# Rth.net
KiCad netlist of a schematic drawn in Altium Designer
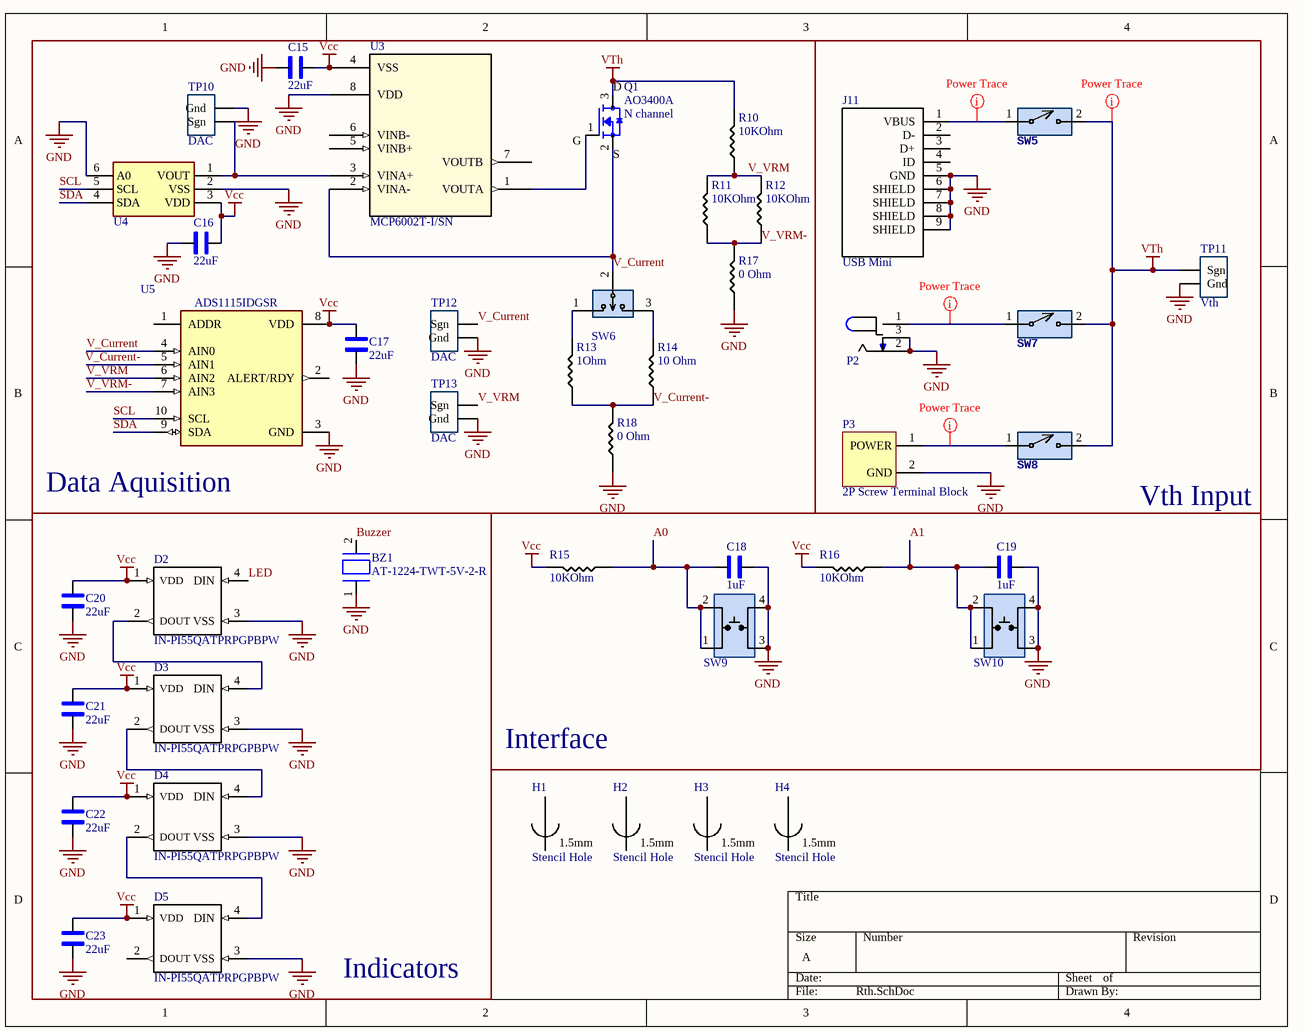
[diagram p0: Rth.SchDoc]

(export (version "E")
  (design (tool "Eeschema 10.0.6"))
  (components
    (comp (ref "BZ1")
      (value "AT-1224-TWT-5V-2-R")
      (footprint "BUZZER- TH")
      (fields (field (name "MFR PART #") "AT-1224-TWT-5V-2-R"))
      (libsource (lib "ECEN5730Lib_2023_01_DS") (part "BUZZER_1"))
    )
    (comp (ref "C15")
      (value "22uF")
      (footprint "1206_Passive_Capacitor")
      (description "22uF ±10% 25V X5R 1206 Multilayer Ceramic Capacitors MLCC - SMD/SMT RoHS")
      (fields (field (name "MFR PART #") "CL31A226KAHNNNE") (field (name "LCSC PART#") "C12891"))
      (libsource (lib "ECEN5730Lib_2023_01_DS") (part "C_22uF_1206"))
    )
    (comp (ref "C16")
      (value "22uF")
      (footprint "1206_Passive_Capacitor")
      (description "22uF ±10% 25V X5R 1206 Multilayer Ceramic Capacitors MLCC - SMD/SMT RoHS")
      (fields (field (name "MFR PART #") "CL31A226KAHNNNE") (field (name "LCSC PART#") "C12891"))
      (libsource (lib "ECEN5730Lib_2023_01_DS") (part "C_22uF_1206"))
    )
    (comp (ref "C17")
      (value "22uF")
      (footprint "1206_Passive_Capacitor")
      (description "22uF ±10% 25V X5R 1206 Multilayer Ceramic Capacitors MLCC - SMD/SMT RoHS")
      (fields (field (name "MFR PART #") "CL31A226KAHNNNE") (field (name "LCSC PART#") "C12891"))
      (libsource (lib "ECEN5730Lib_2023_01_DS") (part "C_22uF_1206"))
    )
    (comp (ref "C18")
      (value "1uF")
      (footprint "1206_Passive_Capacitor")
      (description "MULTILAYER CERAMIC CAPACITORS MLCC - SMD/SMT 1UF 50V 1206 ROHS")
      (fields (field (name "MFR PART #") "CL31B105KBHNNNE") (field (name "LCSC PART#") "C1848"))
      (libsource (lib "ECEN5730Lib_2023_01_DS") (part "C_1uF_1206"))
    )
    (comp (ref "C19")
      (value "1uF")
      (footprint "1206_Passive_Capacitor")
      (description "MULTILAYER CERAMIC CAPACITORS MLCC - SMD/SMT 1UF 50V 1206 ROHS")
      (fields (field (name "MFR PART #") "CL31B105KBHNNNE") (field (name "LCSC PART#") "C1848"))
      (libsource (lib "ECEN5730Lib_2023_01_DS") (part "C_1uF_1206"))
    )
    (comp (ref "C20")
      (value "22uF")
      (footprint "1206_Passive_Capacitor")
      (description "22uF ±10% 25V X5R 1206 Multilayer Ceramic Capacitors MLCC - SMD/SMT RoHS")
      (fields (field (name "MFR PART #") "CL31A226KAHNNNE") (field (name "LCSC PART#") "C12891"))
      (libsource (lib "ECEN5730Lib_2023_01_DS") (part "C_22uF_1206"))
    )
    (comp (ref "C21")
      (value "22uF")
      (footprint "1206_Passive_Capacitor")
      (description "22uF ±10% 25V X5R 1206 Multilayer Ceramic Capacitors MLCC - SMD/SMT RoHS")
      (fields (field (name "MFR PART #") "CL31A226KAHNNNE") (field (name "LCSC PART#") "C12891"))
      (libsource (lib "ECEN5730Lib_2023_01_DS") (part "C_22uF_1206"))
    )
    (comp (ref "C22")
      (value "22uF")
      (footprint "1206_Passive_Capacitor")
      (description "22uF ±10% 25V X5R 1206 Multilayer Ceramic Capacitors MLCC - SMD/SMT RoHS")
      (fields (field (name "MFR PART #") "CL31A226KAHNNNE") (field (name "LCSC PART#") "C12891"))
      (libsource (lib "ECEN5730Lib_2023_01_DS") (part "C_22uF_1206"))
    )
    (comp (ref "C23")
      (value "22uF")
      (footprint "1206_Passive_Capacitor")
      (description "22uF ±10% 25V X5R 1206 Multilayer Ceramic Capacitors MLCC - SMD/SMT RoHS")
      (fields (field (name "MFR PART #") "CL31A226KAHNNNE") (field (name "LCSC PART#") "C12891"))
      (libsource (lib "ECEN5730Lib_2023_01_DS") (part "C_22uF_1206"))
    )
    (comp (ref "D2")
      (value "IN-PI55QATPRPGPBPW")
      (footprint "SERIAL_LED - duplicate")
      (fields
        (field (name "LCSC PART#") "C2761795")
        (field (name "MFR PART #") "IN-PI55QATPRPGPBPW-60")
        (field (name "MANUFACTURER") "Inolux")
      )
      (libsource (lib "ECEN5730Lib_2023_01_DS") (part "LED_Smart"))
    )
    (comp (ref "D3")
      (value "IN-PI55QATPRPGPBPW")
      (footprint "SERIAL_LED - duplicate")
      (fields
        (field (name "LCSC PART#") "C2761795")
        (field (name "MFR PART #") "IN-PI55QATPRPGPBPW-60")
        (field (name "MANUFACTURER") "Inolux")
      )
      (libsource (lib "ECEN5730Lib_2023_01_DS") (part "LED_Smart"))
    )
    (comp (ref "D4")
      (value "IN-PI55QATPRPGPBPW")
      (footprint "SERIAL_LED - duplicate")
      (fields
        (field (name "LCSC PART#") "C2761795")
        (field (name "MFR PART #") "IN-PI55QATPRPGPBPW-60")
        (field (name "MANUFACTURER") "Inolux")
      )
      (libsource (lib "ECEN5730Lib_2023_01_DS") (part "LED_Smart"))
    )
    (comp (ref "D5")
      (value "IN-PI55QATPRPGPBPW")
      (footprint "SERIAL_LED - duplicate")
      (fields
        (field (name "LCSC PART#") "C2761795")
        (field (name "MFR PART #") "IN-PI55QATPRPGPBPW-60")
        (field (name "MANUFACTURER") "Inolux")
      )
      (libsource (lib "ECEN5730Lib_2023_01_DS") (part "LED_Smart"))
    )
    (comp (ref "H1")
      (value "Stencil Hole")
      (footprint "AlignmentHole_1.5mm")
      (description "Stencil Allignment hole for use with 1.5mm pin")
      (libsource (lib "ECEN5730Lib_2023_01_DS") (part "H_StencilAllignment_1.5mm"))
    )
    (comp (ref "H2")
      (value "Stencil Hole")
      (footprint "AlignmentHole_1.5mm")
      (description "Stencil Allignment hole for use with 1.5mm pin")
      (libsource (lib "ECEN5730Lib_2023_01_DS") (part "H_StencilAllignment_1.5mm"))
    )
    (comp (ref "H3")
      (value "Stencil Hole")
      (footprint "AlignmentHole_1.5mm")
      (description "Stencil Allignment hole for use with 1.5mm pin")
      (libsource (lib "ECEN5730Lib_2023_01_DS") (part "H_StencilAllignment_1.5mm"))
    )
    (comp (ref "H4")
      (value "Stencil Hole")
      (footprint "AlignmentHole_1.5mm")
      (description "Stencil Allignment hole for use with 1.5mm pin")
      (libsource (lib "ECEN5730Lib_2023_01_DS") (part "H_StencilAllignment_1.5mm"))
    )
    (comp (ref "J11")
      (value "USB Mini")
      (footprint "USB_MINI_B")
      (description "Through Hole USB Connectors RoHS")
      (fields (field (name "LCSC PART#") "C46398") (field (name "MFR PART #") "920-462A2021D10102"))
      (libsource (lib "ECEN5730Lib_2023_01_DS") (part "J_USB_B_Mini"))
    )
    (comp (ref "P2")
      (value "Power Jack")
      (footprint "Power_Jack")
      (description "Power Barrel Connector Jack 2.10mm ID (0.083\"), 5.50mm OD (0.217\") Through Hole, Right Angle")
      (fields (field (name "MFR PART #") "PJ-102A") (field (name "LCSC PART#") "C136744"))
      (libsource (lib "ECEN5730Lib_2023_01_DS") (part "P_Power Jack"))
    )
    (comp (ref "P3")
      (value "2P Screw Terminal Block")
      (footprint "P_Terminal block 3.5mm-pitch")
      (description "Green Straight pin 3.5mm  pitch; P=3.5mm  Screw terminal ROHS")
      (fields (field (name "MFR PART #") "KF350-3.5-2P") (field (name "MANUFACTURER") "Cixi Kefa Elec"))
      (libsource (lib "ECEN5730Lib_2023_01_DS") (part "P_Terminal block"))
    )
    (comp (ref "Q1")
      (value "AO3400A")
      (footprint "N-MOSFET")
      (description "MOSFET N Trench 30V 5.7A 1.5V @ 250uA 26.5 m? @ 5.7A,10V SOT-23-3L RoHS")
      (fields (field (name "LCSC PART#") "C20917") (field (name "ALTIUM_VALUE") "N channel"))
      (libsource (lib "ECEN5730Lib_2023_01_DS") (part "Q_Nch_MOSFET"))
    )
    (comp (ref "R10")
      (value "10KOhm")
      (footprint "1206_Passive_Resitor")
      (description "10 kOhms ±5% 0.25W, 1/4W Chip Resistor 1206 (3216 Metric) Automotive AEC-Q200 Thick Film")
      (fields (field (name "MFR PART #") "RMCF1206FT10K0") (field (name "LCSC PART#") "C17902"))
      (libsource (lib "ECEN5730Lib_2023_01_DS") (part "R_10KOhm_1206"))
    )
    (comp (ref "R11")
      (value "10KOhm")
      (footprint "1206_Passive_Resitor")
      (description "10 kOhms ±5% 0.25W, 1/4W Chip Resistor 1206 (3216 Metric) Automotive AEC-Q200 Thick Film")
      (fields (field (name "MFR PART #") "RMCF1206FT10K0") (field (name "LCSC PART#") "C17902"))
      (libsource (lib "ECEN5730Lib_2023_01_DS") (part "R_10KOhm_1206"))
    )
    (comp (ref "R12")
      (value "10KOhm")
      (footprint "1206_Passive_Resitor")
      (description "10 kOhms ±5% 0.25W, 1/4W Chip Resistor 1206 (3216 Metric) Automotive AEC-Q200 Thick Film")
      (fields (field (name "MFR PART #") "RMCF1206FT10K0") (field (name "LCSC PART#") "C17902"))
      (libsource (lib "ECEN5730Lib_2023_01_DS") (part "R_10KOhm_1206"))
    )
    (comp (ref "R13")
      (value "1Ohm")
      (footprint "1206_Passive_Resitor")
      (description "1Ω ±5% 0.25W ±400ppm/℃ 1206 Chip Resistor - Surface Mount RoHS")
      (fields (field (name "LCSC PART#") "C1409") (field (name "MFR PART #") "1206W4J010JT5E"))
      (libsource (lib "ECEN5730Lib_2023_01_DS") (part "R_1Ohm_1206"))
    )
    (comp (ref "R14")
      (value "10 Ohm")
      (footprint "1206_Passive_Resitor")
      (description "CHIP RESISTOR - SURFACE MOUNT 0.1OHMS ±1% 1/4W 1206 ROHS")
      (fields (field (name "MFR PART #") "1206W4F100JT5E") (field (name "LCSC PART#") "C17903"))
      (libsource (lib "ECEN5730Lib_2023_01_DS") (part "R_10Ohm_1206"))
    )
    (comp (ref "R15")
      (value "10KOhm")
      (footprint "1206_Passive_Resitor")
      (description "10 kOhms ±5% 0.25W, 1/4W Chip Resistor 1206 (3216 Metric) Automotive AEC-Q200 Thick Film")
      (fields (field (name "MFR PART #") "RMCF1206FT10K0") (field (name "LCSC PART#") "C17902"))
      (libsource (lib "ECEN5730Lib_2023_01_DS") (part "R_10KOhm_1206"))
    )
    (comp (ref "R16")
      (value "10KOhm")
      (footprint "1206_Passive_Resitor")
      (description "10 kOhms ±5% 0.25W, 1/4W Chip Resistor 1206 (3216 Metric) Automotive AEC-Q200 Thick Film")
      (fields (field (name "MFR PART #") "RMCF1206FT10K0") (field (name "LCSC PART#") "C17902"))
      (libsource (lib "ECEN5730Lib_2023_01_DS") (part "R_10KOhm_1206"))
    )
    (comp (ref "R17")
      (value "0 Ohm")
      (footprint "1206_Passive_Resitor")
      (description "CHIP RESISTOR - SURFACE MOUNT 0OHMS ±1% 1/4W 1206 ROHS")
      (fields (field (name "MFR PART #") "1206W4F0000T5E") (field (name "LCSC PART#") "C17888"))
      (libsource (lib "ECEN5730Lib_2023_01_DS") (part "R_0Ohm_1206"))
    )
    (comp (ref "R18")
      (value "0 Ohm")
      (footprint "1206_Passive_Resitor")
      (description "CHIP RESISTOR - SURFACE MOUNT 0OHMS ±1% 1/4W 1206 ROHS")
      (fields (field (name "MFR PART #") "1206W4F0000T5E") (field (name "LCSC PART#") "C17888"))
      (libsource (lib "ECEN5730Lib_2023_01_DS") (part "R_0Ohm_1206"))
    )
    (comp (ref "SW5")
      (value "SW_2Pin_100mil_Switch")
      (footprint "2Pin-Header-Conn")
      (description "2Pin Header")
      (fields (field (name "LCSC PART#") "C124375"))
      (libsource (lib "ECEN5730Lib_2023_01_DS") (part "SW_2Pin_100mil_Switch"))
    )
    (comp (ref "SW6")
      (value "PREC003SAAN-RC")
      (footprint "3_PIN_100mil")
      (description "Connector Header Through Hole 3 position 0.100\" (2.54mm)")
      (fields (field (name "LCSC PART#") "C49257"))
      (libsource (lib "ECEN5730Lib_2023_01_DS") (part "SW_3Pin_100mil_Switch"))
    )
    (comp (ref "SW7")
      (value "SW_2Pin_100mil_Switch")
      (footprint "2Pin-Header-Conn")
      (description "2Pin Header")
      (fields (field (name "LCSC PART#") "C124375"))
      (libsource (lib "ECEN5730Lib_2023_01_DS") (part "SW_2Pin_100mil_Switch"))
    )
    (comp (ref "SW8")
      (value "SW_2Pin_100mil_Switch")
      (footprint "2Pin-Header-Conn")
      (description "2Pin Header")
      (fields (field (name "LCSC PART#") "C124375"))
      (libsource (lib "ECEN5730Lib_2023_01_DS") (part "SW_2Pin_100mil_Switch"))
    )
    (comp (ref "SW9")
      (value "TL3305AF160QG")
      (footprint "Switch_JLC")
      (description "Tactile Switch SPST-NO Top Actuated Surface Mount")
      (fields (field (name "MFR PART #") "KH-4.5X4.5X4.3H-STM") (field (name "LCSC PART#") "C2837550"))
      (libsource (lib "ECEN5730Lib_2023_01_DS") (part "SW_Push_Button_JLC"))
    )
    (comp (ref "SW10")
      (value "TL3305AF160QG")
      (footprint "Switch_JLC")
      (description "Tactile Switch SPST-NO Top Actuated Surface Mount")
      (fields (field (name "MFR PART #") "KH-4.5X4.5X4.3H-STM") (field (name "LCSC PART#") "C2837550"))
      (libsource (lib "ECEN5730Lib_2023_01_DS") (part "SW_Push_Button_JLC"))
    )
    (comp (ref "TP10")
      (value "DAC")
      (footprint "TP10x_Probe")
      (description "Test Point 300 mil centers")
      (libsource (lib "") (part "TP_10x_Probe_2"))
    )
    (comp (ref "TP11")
      (value "Vth")
      (footprint "TP10x_Probe")
      (description "Test Point 300 mil centers")
      (libsource (lib "") (part "TP_10x_Probe_1"))
    )
    (comp (ref "TP12")
      (value "DAC")
      (footprint "TP10x_Probe")
      (description "Test Point 300 mil centers")
      (libsource (lib "ECEN5730Lib_2023_01_DS") (part "TP_10x_Probe"))
    )
    (comp (ref "TP13")
      (value "DAC")
      (footprint "TP10x_Probe")
      (description "Test Point 300 mil centers")
      (libsource (lib "ECEN5730Lib_2023_01_DS") (part "TP_10x_Probe"))
    )
    (comp (ref "U3")
      (value "MCP6002T-I/SN")
      (footprint "SOIC127P600X175-8N")
      (description "0.6 V/us 2 1MHz 1.8V ~ 6V 100μA General Purpose SOIC-8_150mil  Operational Amplifier ROHS")
      (fields (field (name "MFR") "Microchip") (field (name "LCSC PART#") "C7377"))
      (libsource (lib "ECEN5730Lib_2023_01_DS") (part "U_MCP6002T-I/SN"))
    )
    (comp (ref "U4")
      (value "DAC IC")
      (footprint "MCP4725")
      (description "IC DAC 12BIT V-OUT SOT23-6")
      (fields (field (name "LCSC PART#") "C144198") (field (name "MFR PART #") "MCP4725A0T-E/CH"))
      (libsource (lib "ECEN5730Lib_2023_01_DS") (part "U_MCP4725A0T-E/CH"))
    )
    (comp (ref "U5")
      (value "ADS1115IDGSR")
      (footprint "ADC_ADS1115IDGSR")
      (description "16-Bit ADC with Integrated MUX, PGA, Comparator, Oscillator, and Reference 10-VSSOP -40 to 125")
      (fields (field (name "LCSC PART#") "C37593"))
      (libsource (lib "ECEN5730Lib_2023_01_DS") (part "U_ADC_ADS1115IDGSR"))
    )
  )
  (nets
    (net (code "1") (name "/A0") (class "Default")
      (node (ref "C18") (pin "2") (pinfunction "2_2") (pintype "passive"))
      (node (ref "R15") (pin "1") (pinfunction "1_1") (pintype "passive"))
      (node (ref "SW9") (pin "1") (pinfunction "1_1") (pintype "passive"))
      (node (ref "SW9") (pin "2") (pinfunction "2_2") (pintype "passive"))
    )
    (net (code "2") (name "/A1") (class "Default")
      (node (ref "C19") (pin "2") (pinfunction "2_2") (pintype "passive"))
      (node (ref "R16") (pin "1") (pinfunction "1_1") (pintype "passive"))
      (node (ref "SW10") (pin "1") (pinfunction "1_1") (pintype "passive"))
      (node (ref "SW10") (pin "2") (pinfunction "2_2") (pintype "passive"))
    )
    (net (code "3") (name "/Buzzer") (class "Default")
      (node (ref "BZ1") (pin "2") (pinfunction "BZ2_2") (pintype "passive"))
    )
    (net (code "4") (name "/LED") (class "Default")
      (node (ref "D2") (pin "4") (pinfunction "DIN_4") (pintype "input"))
    )
    (net (code "5") (name "/SCL") (class "Default")
      (node (ref "U4") (pin "5") (pinfunction "SCL_5") (pintype "passive"))
      (node (ref "U5") (pin "10") (pinfunction "SCL_10") (pintype "input"))
    )
    (net (code "6") (name "/SDA") (class "Default")
      (node (ref "U4") (pin "4") (pinfunction "SDA_4") (pintype "passive"))
      (node (ref "U5") (pin "9") (pinfunction "SDA_9") (pintype "bidirectional"))
    )
    (net (code "7") (name "/V_Current") (class "Default")
      (node (ref "Q1") (pin "2") (pinfunction "S_2") (pintype "passive"))
      (node (ref "SW6") (pin "2") (pinfunction "2_2") (pintype "passive"))
      (node (ref "TP12") (pin "1") (pinfunction "Sgn_1") (pintype "passive"))
      (node (ref "U3") (pin "2") (pinfunction "VINA-_2") (pintype "input"))
      (node (ref "U5") (pin "4") (pinfunction "AIN0_4") (pintype "input"))
    )
    (net (code "8") (name "/V_Current-") (class "Default")
      (node (ref "R13") (pin "1") (pinfunction "1_1") (pintype "passive"))
      (node (ref "R14") (pin "1") (pinfunction "1_1") (pintype "passive"))
      (node (ref "R18") (pin "2") (pinfunction "2_2") (pintype "passive"))
    )
    (net (code "9") (name "/V_VRM") (class "Default")
      (node (ref "R10") (pin "1") (pinfunction "1_1") (pintype "passive"))
      (node (ref "R11") (pin "2") (pinfunction "2_2") (pintype "passive"))
      (node (ref "R12") (pin "2") (pinfunction "2_2") (pintype "passive"))
      (node (ref "TP13") (pin "1") (pinfunction "Sgn_1") (pintype "passive"))
      (node (ref "U5") (pin "6") (pinfunction "AIN2_6") (pintype "input"))
    )
    (net (code "10") (name "/V_VRM-") (class "Default")
      (node (ref "R11") (pin "1") (pinfunction "1_1") (pintype "passive"))
      (node (ref "R12") (pin "1") (pinfunction "1_1") (pintype "passive"))
      (node (ref "R17") (pin "2") (pinfunction "2_2") (pintype "passive"))
      (node (ref "U5") (pin "7") (pinfunction "AIN3_7") (pintype "input"))
    )
    (net (code "11") (name "GND") (class "Default")
      (node (ref "BZ1") (pin "1") (pinfunction "BZ1_1") (pintype "passive"))
      (node (ref "C15") (pin "1") (pinfunction "1_1") (pintype "passive"))
      (node (ref "C16") (pin "1") (pinfunction "1_1") (pintype "passive"))
      (node (ref "C17") (pin "1") (pinfunction "1_1") (pintype "passive"))
      (node (ref "C18") (pin "1") (pinfunction "1_1") (pintype "passive"))
      (node (ref "C19") (pin "1") (pinfunction "1_1") (pintype "passive"))
      (node (ref "C20") (pin "1") (pinfunction "1_1") (pintype "passive"))
      (node (ref "C21") (pin "1") (pinfunction "1_1") (pintype "passive"))
      (node (ref "C22") (pin "1") (pinfunction "1_1") (pintype "passive"))
      (node (ref "C23") (pin "1") (pinfunction "1_1") (pintype "passive"))
      (node (ref "D2") (pin "3") (pinfunction "VSS_3") (pintype "input"))
      (node (ref "D3") (pin "3") (pinfunction "VSS_3") (pintype "input"))
      (node (ref "D4") (pin "3") (pinfunction "VSS_3") (pintype "input"))
      (node (ref "D5") (pin "3") (pinfunction "VSS_3") (pintype "input"))
      (node (ref "J11") (pin "5") (pinfunction "GND_5") (pintype "passive"))
      (node (ref "J11") (pin "6") (pinfunction "SHIELD_6") (pintype "passive"))
      (node (ref "J11") (pin "7") (pinfunction "SHIELD_7") (pintype "passive"))
      (node (ref "J11") (pin "8") (pinfunction "SHIELD_8") (pintype "passive"))
      (node (ref "J11") (pin "9") (pinfunction "SHIELD_9") (pintype "passive"))
      (node (ref "P2") (pin "2") (pinfunction "2_2") (pintype "power_in"))
      (node (ref "P2") (pin "3") (pinfunction "3_3") (pintype "power_in"))
      (node (ref "P3") (pin "2") (pinfunction "GND_2") (pintype "passive"))
      (node (ref "R17") (pin "1") (pinfunction "1_1") (pintype "passive"))
      (node (ref "R18") (pin "1") (pinfunction "1_1") (pintype "passive"))
      (node (ref "SW10") (pin "3") (pinfunction "3_3") (pintype "passive"))
      (node (ref "SW10") (pin "4") (pinfunction "4_4") (pintype "passive"))
      (node (ref "SW9") (pin "3") (pinfunction "3_3") (pintype "passive"))
      (node (ref "SW9") (pin "4") (pinfunction "4_4") (pintype "passive"))
      (node (ref "TP10") (pin "2") (pinfunction "Gnd_2") (pintype "passive"))
      (node (ref "TP11") (pin "2") (pinfunction "Gnd_2") (pintype "passive"))
      (node (ref "TP12") (pin "2") (pinfunction "Gnd_2") (pintype "passive"))
      (node (ref "TP13") (pin "2") (pinfunction "Gnd_2") (pintype "passive"))
      (node (ref "U3") (pin "8") (pinfunction "VDD_8") (pintype "passive"))
      (node (ref "U4") (pin "2") (pinfunction "VSS_2") (pintype "passive"))
      (node (ref "U4") (pin "6") (pinfunction "A0_6") (pintype "passive"))
      (node (ref "U5") (pin "3") (pinfunction "GND_3") (pintype "power_in"))
    )
    (net (code "12") (name "Net-(D2-DOUT)") (class "Default")
      (node (ref "D2") (pin "2") (pinfunction "DOUT_2") (pintype "output"))
      (node (ref "D3") (pin "4") (pinfunction "DIN_4") (pintype "input"))
    )
    (net (code "13") (name "Net-(D3-DOUT)") (class "Default")
      (node (ref "D3") (pin "2") (pinfunction "DOUT_2") (pintype "output"))
      (node (ref "D4") (pin "4") (pinfunction "DIN_4") (pintype "input"))
    )
    (net (code "14") (name "Net-(D4-DOUT)") (class "Default")
      (node (ref "D4") (pin "2") (pinfunction "DOUT_2") (pintype "output"))
      (node (ref "D5") (pin "4") (pinfunction "DIN_4") (pintype "input"))
    )
    (net (code "15") (name "Net-(J11-VBUS)") (class "Default")
      (node (ref "J11") (pin "1") (pinfunction "VBUS_1") (pintype "passive"))
      (node (ref "SW5") (pin "1") (pinfunction "1_1") (pintype "passive"))
    )
    (net (code "16") (name "Net-(P2-Pad1)") (class "Default")
      (node (ref "P2") (pin "1") (pinfunction "1_1") (pintype "power_in"))
      (node (ref "SW7") (pin "1") (pinfunction "1_1") (pintype "passive"))
    )
    (net (code "17") (name "Net-(P3-POWER)") (class "Default")
      (node (ref "P3") (pin "1") (pinfunction "POWER_1") (pintype "passive"))
      (node (ref "SW8") (pin "1") (pinfunction "1_1") (pintype "passive"))
    )
    (net (code "18") (name "Net-(Q1-G)") (class "Default")
      (node (ref "Q1") (pin "1") (pinfunction "G_1") (pintype "passive"))
      (node (ref "U3") (pin "1") (pinfunction "VOUTA_1") (pintype "output"))
    )
    (net (code "19") (name "Net-(R13-Pad2)") (class "Default")
      (node (ref "R13") (pin "2") (pinfunction "2_2") (pintype "passive"))
      (node (ref "SW6") (pin "1") (pinfunction "1_1") (pintype "passive"))
    )
    (net (code "20") (name "Net-(R14-Pad2)") (class "Default")
      (node (ref "R14") (pin "2") (pinfunction "2_2") (pintype "passive"))
      (node (ref "SW6") (pin "3") (pinfunction "3_3") (pintype "passive"))
    )
    (net (code "21") (name "Net-(TP10-Sgn)") (class "Default")
      (node (ref "TP10") (pin "1") (pinfunction "Sgn_1") (pintype "passive"))
      (node (ref "U3") (pin "3") (pinfunction "VINA+_3") (pintype "input"))
      (node (ref "U4") (pin "1") (pinfunction "VOUT_1") (pintype "passive"))
    )
    (net (code "22") (name "VTh") (class "Default")
      (node (ref "Q1") (pin "3") (pinfunction "D_3") (pintype "passive"))
      (node (ref "R10") (pin "2") (pinfunction "2_2") (pintype "passive"))
      (node (ref "SW5") (pin "2") (pinfunction "2_2") (pintype "passive"))
      (node (ref "SW7") (pin "2") (pinfunction "2_2") (pintype "passive"))
      (node (ref "SW8") (pin "2") (pinfunction "2_2") (pintype "passive"))
      (node (ref "TP11") (pin "1") (pinfunction "Sgn_1") (pintype "passive"))
    )
    (net (code "23") (name "Vcc") (class "Default")
      (node (ref "C15") (pin "2") (pinfunction "2_2") (pintype "passive"))
      (node (ref "C16") (pin "2") (pinfunction "2_2") (pintype "passive"))
      (node (ref "C17") (pin "2") (pinfunction "2_2") (pintype "passive"))
      (node (ref "C20") (pin "2") (pinfunction "2_2") (pintype "passive"))
      (node (ref "C21") (pin "2") (pinfunction "2_2") (pintype "passive"))
      (node (ref "C22") (pin "2") (pinfunction "2_2") (pintype "passive"))
      (node (ref "C23") (pin "2") (pinfunction "2_2") (pintype "passive"))
      (node (ref "D2") (pin "1") (pinfunction "VDD_1") (pintype "input"))
      (node (ref "D3") (pin "1") (pinfunction "VDD_1") (pintype "input"))
      (node (ref "D4") (pin "1") (pinfunction "VDD_1") (pintype "input"))
      (node (ref "D5") (pin "1") (pinfunction "VDD_1") (pintype "input"))
      (node (ref "R15") (pin "2") (pinfunction "2_2") (pintype "passive"))
      (node (ref "R16") (pin "2") (pinfunction "2_2") (pintype "passive"))
      (node (ref "U3") (pin "4") (pinfunction "VSS_4") (pintype "passive"))
      (node (ref "U4") (pin "3") (pinfunction "VDD_3") (pintype "passive"))
      (node (ref "U5") (pin "8") (pinfunction "VDD_8") (pintype "power_in"))
    )
    (net (code "24") (name "unconnected-(D5-DOUT-Pad2)") (class "Default")
      (node (ref "D5") (pin "2") (pinfunction "DOUT_2") (pintype "output"))
    )
    (net (code "25") (name "unconnected-(J11-D+-Pad3)") (class "Default")
      (node (ref "J11") (pin "3") (pinfunction "D+_3") (pintype "passive"))
    )
    (net (code "26") (name "unconnected-(J11-D--Pad2)") (class "Default")
      (node (ref "J11") (pin "2") (pinfunction "D-_2") (pintype "passive"))
    )
    (net (code "27") (name "unconnected-(J11-ID-Pad4)") (class "Default")
      (node (ref "J11") (pin "4") (pinfunction "ID_4") (pintype "passive"))
    )
    (net (code "28") (name "unconnected-(U3-VINB+-Pad5)") (class "Default")
      (node (ref "U3") (pin "5") (pinfunction "VINB+_5") (pintype "input"))
    )
    (net (code "29") (name "unconnected-(U3-VINB--Pad6)") (class "Default")
      (node (ref "U3") (pin "6") (pinfunction "VINB-_6") (pintype "input"))
    )
    (net (code "30") (name "unconnected-(U3-VOUTB-Pad7)") (class "Default")
      (node (ref "U3") (pin "7") (pinfunction "VOUTB_7") (pintype "output"))
    )
    (net (code "31") (name "unconnected-(U5-ADDR-Pad1)") (class "Default")
      (node (ref "U5") (pin "1") (pinfunction "ADDR_1") (pintype "passive"))
    )
    (net (code "32") (name "unconnected-(U5-AIN1-Pad5)") (class "Default")
      (node (ref "U5") (pin "5") (pinfunction "AIN1_5") (pintype "input"))
    )
    (net (code "33") (name "unconnected-(U5-ALERT{slash}RDY-Pad2)") (class "Default")
      (node (ref "U5") (pin "2") (pinfunction "ALERT/RDY_2") (pintype "output"))
    )
  )
)
